# Hutschienen-Shield.net
KiCad netlist of a schematic drawn in EAGLE
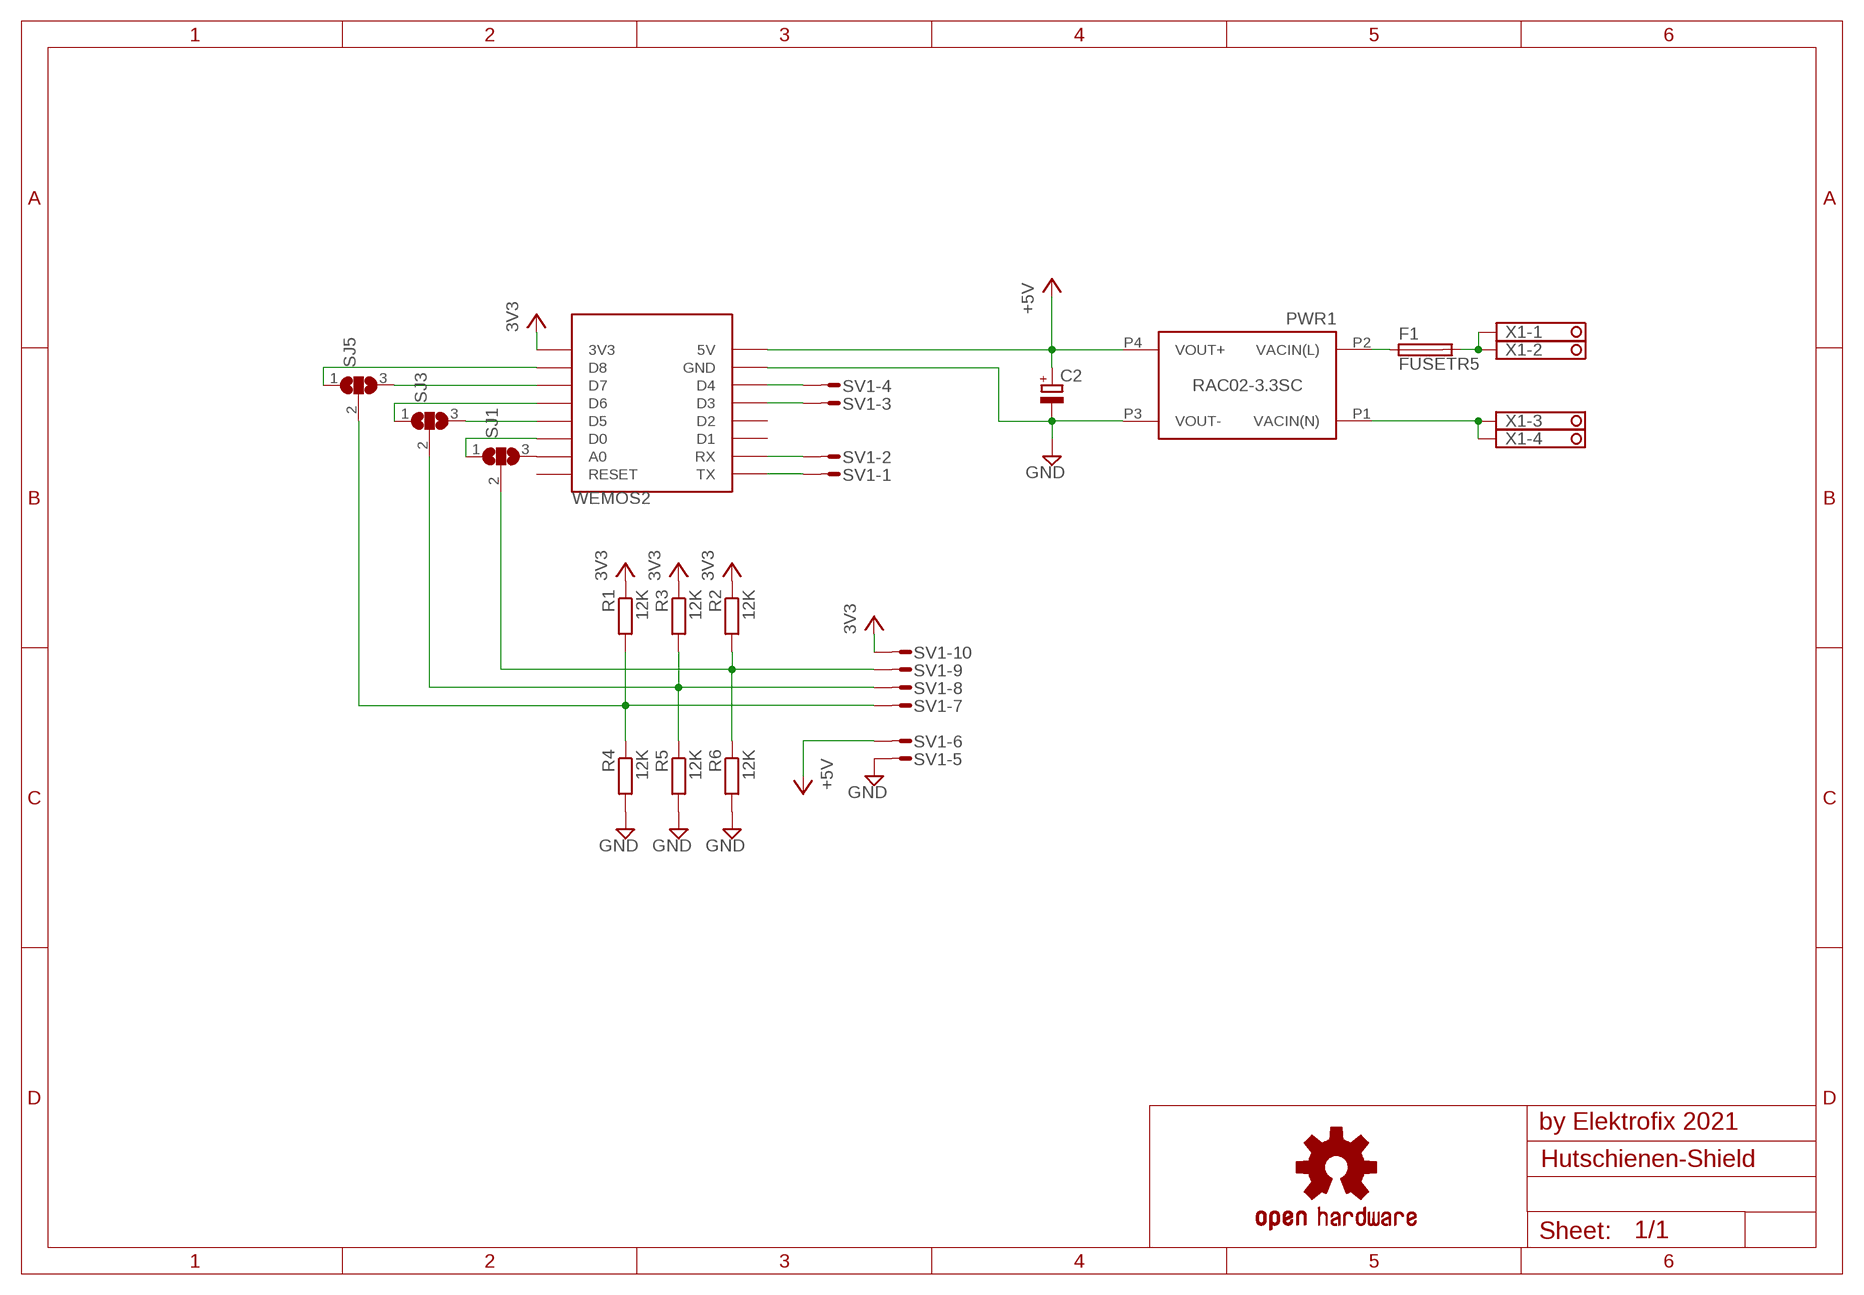
[diagram p0: schematic, sheet 1]

(export (version "E")
  (design (tool "Eeschema 10.0.6"))
  (components
    (comp (ref "C2")
      (value "CPOL-EUE3.5-8")
      (footprint "eagle-import:E3,5-8")
      (libsource (lib "eagle-import") (part "CPOL-EUE3.5-8"))
    )
    (comp (ref "F1")
      (value "FUSETR5")
      (footprint "eagle-import:TR5")
      (libsource (lib "eagle-import") (part "FUSETR5"))
    )
    (comp (ref "LOGO1")
      (value "OSHW-LOGOL")
      (footprint "eagle-import:OSHW-LOGO-L")
      (libsource (lib "eagle-import") (part "OSHW-LOGOL"))
    )
    (comp (ref "PWR1")
      (value "RAC02-3.3SC")
      (footprint "eagle-import:LOW_PROFILE_POWER_MODULE")
      (libsource (lib "eagle-import") (part "RACSC02-3.3"))
    )
    (comp (ref "R1")
      (value "12K")
      (footprint "eagle-import:0207_12")
      (libsource (lib "eagle-import") (part "R-EU_0207/12"))
    )
    (comp (ref "R2")
      (value "12K")
      (footprint "eagle-import:0207_12")
      (libsource (lib "eagle-import") (part "R-EU_0207/12"))
    )
    (comp (ref "R3")
      (value "12K")
      (footprint "eagle-import:0207_12")
      (libsource (lib "eagle-import") (part "R-EU_0207/12"))
    )
    (comp (ref "R4")
      (value "12K")
      (footprint "eagle-import:0207_12")
      (libsource (lib "eagle-import") (part "R-EU_0207/12"))
    )
    (comp (ref "R5")
      (value "12K")
      (footprint "eagle-import:0207_12")
      (libsource (lib "eagle-import") (part "R-EU_0207/12"))
    )
    (comp (ref "R6")
      (value "12K")
      (footprint "eagle-import:0207_12")
      (libsource (lib "eagle-import") (part "R-EU_0207/12"))
    )
    (comp (ref "SJ1")
      (value "SJ2W")
      (footprint "eagle-import:SJ_2")
      (libsource (lib "eagle-import") (part "SJ2W"))
    )
    (comp (ref "SJ3")
      (value "SJ2W")
      (footprint "eagle-import:SJ_2")
      (libsource (lib "eagle-import") (part "SJ2W"))
    )
    (comp (ref "SJ5")
      (value "SJ2W")
      (footprint "eagle-import:SJ_2")
      (libsource (lib "eagle-import") (part "SJ2W"))
    )
    (comp (ref "SV1")
      (value "L10P")
      (footprint "eagle-import:L10P")
      (libsource (lib "eagle-import") (part "L10P"))
    )
    (comp (ref "WEMOS2")
      (value "WEMOS-D1-MINI")
      (footprint "eagle-import:WEMOS-D1-MINI")
      (libsource (lib "eagle-import") (part "WEMOS-D1-MINI"))
    )
    (comp (ref "X1")
      (value "1751264")
      (footprint "eagle-import:1751264")
      (libsource (lib "eagle-import") (part "1751264"))
    )
  )
  (nets
    (net (code "1") (name "+5V") (class "Default")
      (node (ref "C2") (pin "+") (pinfunction "+_+") (pintype "passive"))
      (node (ref "PWR1") (pin "P4") (pinfunction "VOUT+_P4") (pintype "power_in"))
      (node (ref "SV1") (pin "6") (pinfunction "S_6") (pintype "passive"))
      (node (ref "WEMOS2") (pin "5V") (pinfunction "5V_5V") (pintype "bidirectional"))
    )
    (net (code "2") (name "3V3") (class "Default")
      (node (ref "R1") (pin "1") (pinfunction "1_1") (pintype "passive"))
      (node (ref "R2") (pin "1") (pinfunction "1_1") (pintype "passive"))
      (node (ref "R3") (pin "1") (pinfunction "1_1") (pintype "passive"))
      (node (ref "SV1") (pin "10") (pinfunction "S_10") (pintype "passive"))
      (node (ref "WEMOS2") (pin "3V3") (pinfunction "3V3_3V3") (pintype "bidirectional"))
    )
    (net (code "3") (name "GND") (class "Default")
      (node (ref "C2") (pin "-") (pinfunction "-_-") (pintype "passive"))
      (node (ref "PWR1") (pin "P3") (pinfunction "VOUT-_P3") (pintype "power_in"))
      (node (ref "R4") (pin "2") (pinfunction "2_2") (pintype "passive"))
      (node (ref "R5") (pin "2") (pinfunction "2_2") (pintype "passive"))
      (node (ref "R6") (pin "2") (pinfunction "2_2") (pintype "passive"))
      (node (ref "SV1") (pin "5") (pinfunction "S_5") (pintype "passive"))
      (node (ref "WEMOS2") (pin "GND") (pinfunction "GND_GND") (pintype "bidirectional"))
    )
    (net (code "4") (name "Net-(PWR1-VACIN(L))") (class "Default")
      (node (ref "F1") (pin "1") (pinfunction "1_1") (pintype "passive"))
      (node (ref "PWR1") (pin "P2") (pinfunction "VACIN(L)_P2") (pintype "power_in"))
    )
    (net (code "5") (name "Net-(PWR1-VACIN(N))") (class "Default")
      (node (ref "PWR1") (pin "P1") (pinfunction "VACIN(N)_P1") (pintype "power_in"))
      (node (ref "X1") (pin "3") (pinfunction "K_3") (pintype "passive"))
      (node (ref "X1") (pin "4") (pinfunction "K_4") (pintype "passive"))
    )
    (net (code "6") (name "Net-(SJ1-Pad1)") (class "Default")
      (node (ref "SJ1") (pin "1") (pinfunction "1_1") (pintype "passive"))
      (node (ref "WEMOS2") (pin "D0") (pinfunction "D0_D0") (pintype "bidirectional"))
    )
    (net (code "7") (name "Net-(SJ1-Pad3)") (class "Default")
      (node (ref "SJ1") (pin "3") (pinfunction "3_3") (pintype "passive"))
      (node (ref "WEMOS2") (pin "A0") (pinfunction "A0_A0") (pintype "bidirectional"))
    )
    (net (code "8") (name "Net-(SJ3-Pad1)") (class "Default")
      (node (ref "SJ3") (pin "1") (pinfunction "1_1") (pintype "passive"))
      (node (ref "WEMOS2") (pin "D6") (pinfunction "D6_D6") (pintype "bidirectional"))
    )
    (net (code "9") (name "Net-(SJ3-Pad3)") (class "Default")
      (node (ref "SJ3") (pin "3") (pinfunction "3_3") (pintype "passive"))
      (node (ref "WEMOS2") (pin "D5") (pinfunction "D5_D5") (pintype "bidirectional"))
    )
    (net (code "10") (name "Net-(SJ5-Pad1)") (class "Default")
      (node (ref "SJ5") (pin "1") (pinfunction "1_1") (pintype "passive"))
      (node (ref "WEMOS2") (pin "D8") (pinfunction "D8_D8") (pintype "bidirectional"))
    )
    (net (code "11") (name "Net-(SJ5-Pad3)") (class "Default")
      (node (ref "SJ5") (pin "3") (pinfunction "3_3") (pintype "passive"))
      (node (ref "WEMOS2") (pin "D7") (pinfunction "D7_D7") (pintype "bidirectional"))
    )
    (net (code "12") (name "Net-(SV1A-S)") (class "Default")
      (node (ref "SV1") (pin "1") (pinfunction "S_1") (pintype "passive"))
      (node (ref "WEMOS2") (pin "TX") (pinfunction "TX_TX") (pintype "bidirectional"))
    )
    (net (code "13") (name "Net-(SV1C-S)") (class "Default")
      (node (ref "SV1") (pin "2") (pinfunction "S_2") (pintype "passive"))
      (node (ref "WEMOS2") (pin "RX") (pinfunction "RX_RX") (pintype "bidirectional"))
    )
    (net (code "14") (name "Net-(SV1D-S)") (class "Default")
      (node (ref "SV1") (pin "3") (pinfunction "S_3") (pintype "passive"))
      (node (ref "WEMOS2") (pin "D3") (pinfunction "D3_D3") (pintype "bidirectional"))
    )
    (net (code "15") (name "Net-(SV1E-S)") (class "Default")
      (node (ref "SV1") (pin "4") (pinfunction "S_4") (pintype "passive"))
      (node (ref "WEMOS2") (pin "D4") (pinfunction "D4_D4") (pintype "bidirectional"))
    )
    (net (code "16") (name "Net-(SV1H-S)") (class "Default")
      (node (ref "R1") (pin "2") (pinfunction "2_2") (pintype "passive"))
      (node (ref "R4") (pin "1") (pinfunction "1_1") (pintype "passive"))
      (node (ref "SJ5") (pin "2") (pinfunction "2_2") (pintype "passive"))
      (node (ref "SV1") (pin "7") (pinfunction "S_7") (pintype "passive"))
    )
    (net (code "17") (name "Net-(SV1I-S)") (class "Default")
      (node (ref "R3") (pin "2") (pinfunction "2_2") (pintype "passive"))
      (node (ref "R5") (pin "1") (pinfunction "1_1") (pintype "passive"))
      (node (ref "SJ3") (pin "2") (pinfunction "2_2") (pintype "passive"))
      (node (ref "SV1") (pin "8") (pinfunction "S_8") (pintype "passive"))
    )
    (net (code "18") (name "Net-(SV1J-S)") (class "Default")
      (node (ref "R2") (pin "2") (pinfunction "2_2") (pintype "passive"))
      (node (ref "R6") (pin "1") (pinfunction "1_1") (pintype "passive"))
      (node (ref "SJ1") (pin "2") (pinfunction "2_2") (pintype "passive"))
      (node (ref "SV1") (pin "9") (pinfunction "S_9") (pintype "passive"))
    )
    (net (code "19") (name "Net-(X1A-K)") (class "Default")
      (node (ref "F1") (pin "2") (pinfunction "2_2") (pintype "passive"))
      (node (ref "X1") (pin "1") (pinfunction "K_1") (pintype "passive"))
      (node (ref "X1") (pin "2") (pinfunction "K_2") (pintype "passive"))
    )
    (net (code "20") (name "unconnected-(WEMOS2-PadD1)") (class "Default")
      (node (ref "WEMOS2") (pin "D1") (pinfunction "D1_D1") (pintype "bidirectional"))
    )
    (net (code "21") (name "unconnected-(WEMOS2-PadD2)") (class "Default")
      (node (ref "WEMOS2") (pin "D2") (pinfunction "D2_D2") (pintype "bidirectional"))
    )
    (net (code "22") (name "unconnected-(WEMOS2-PadRESET)") (class "Default")
      (node (ref "WEMOS2") (pin "RESET") (pinfunction "RESET_RESET") (pintype "bidirectional"))
    )
  )
)
